# fbd-v1.net
KiCad netlist of a schematic drawn in EAGLE
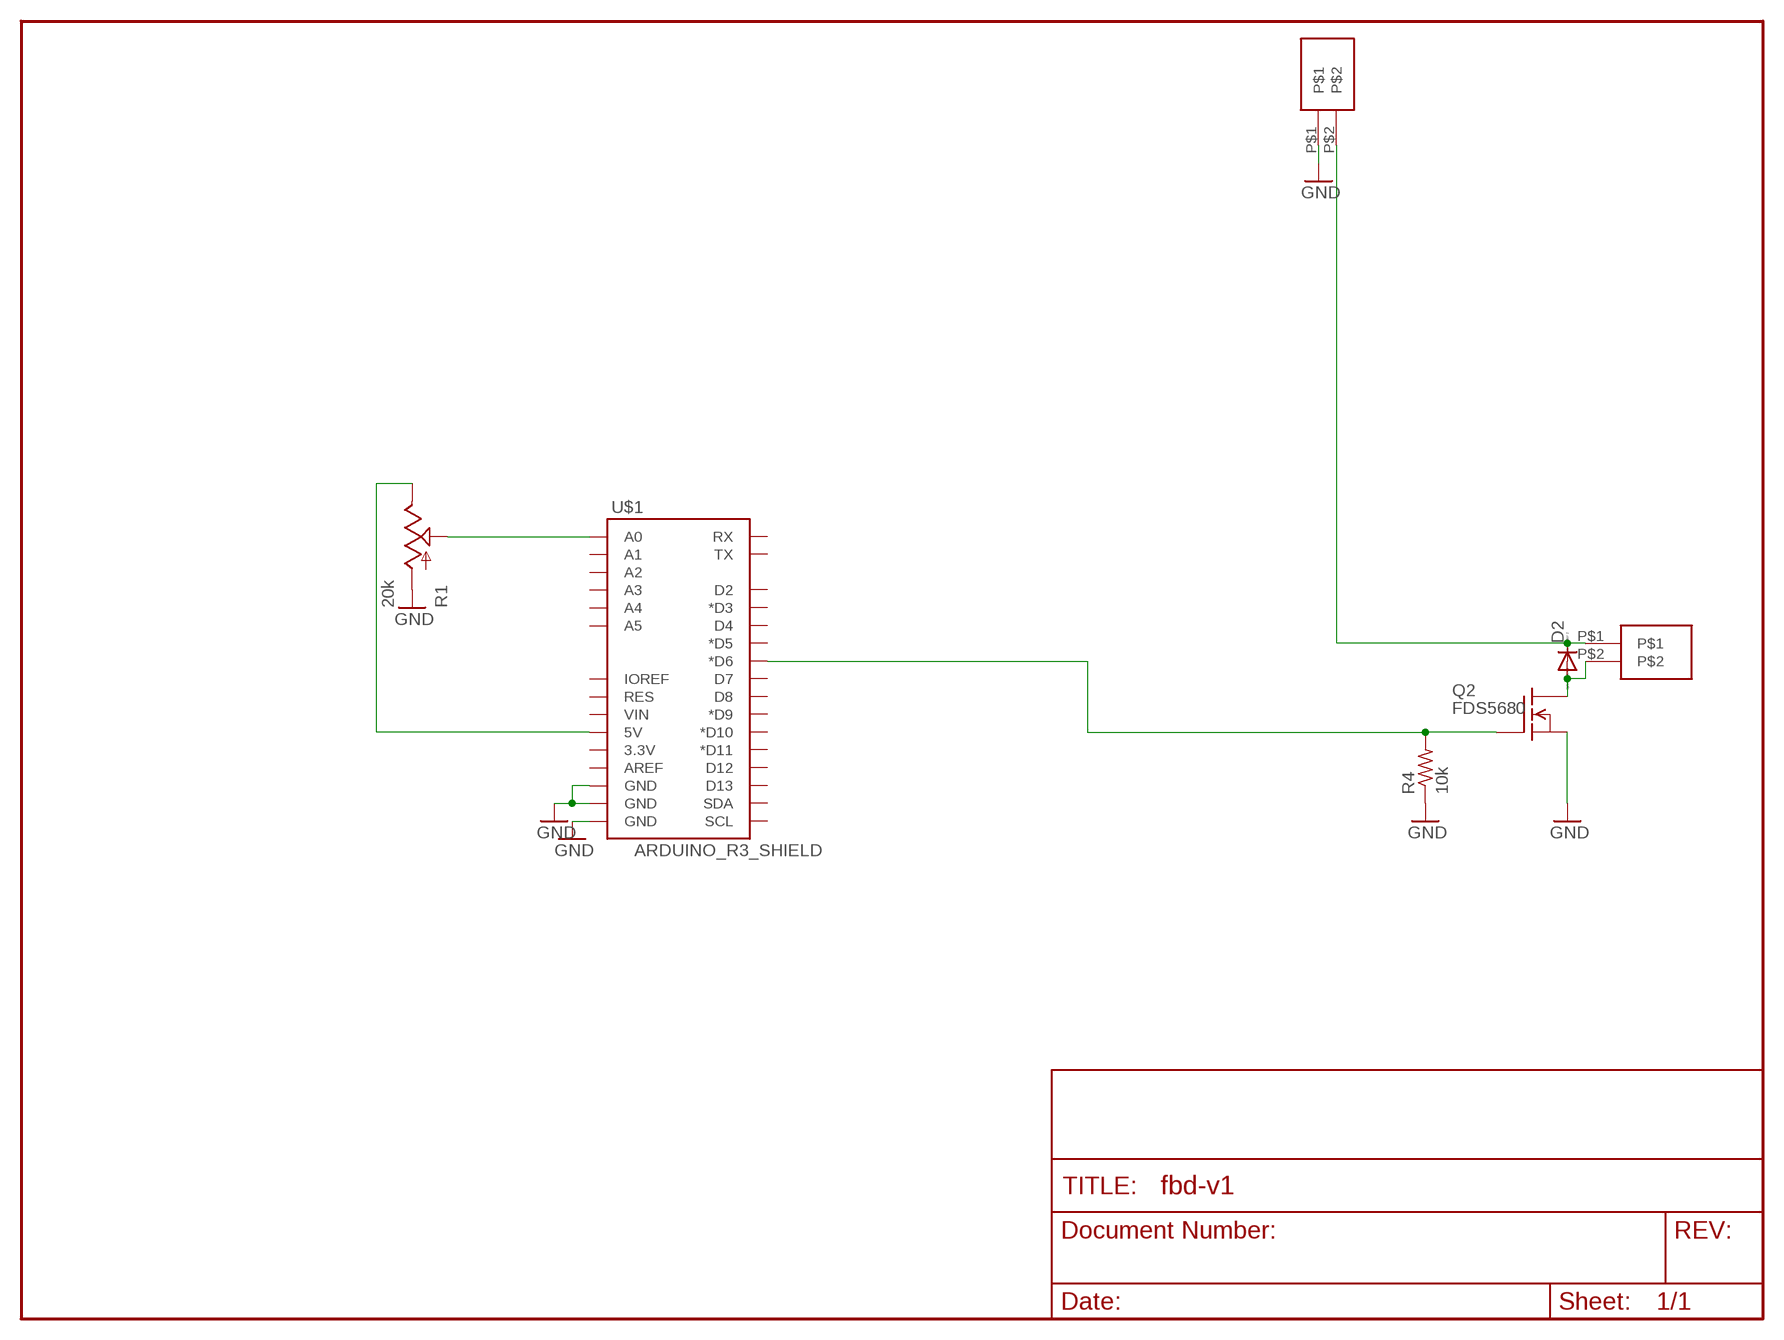
[diagram p0: schematic, sheet 1]

(export (version "E")
  (design (tool "Eeschema 10.0.6"))
  (components
    (comp (ref "D2")
      (value "DIODE-DO-214AC")
      (footprint "eagle-import:DO-214AC")
      (libsource (lib "eagle-import") (part "DIODE-DO-214AC"))
    )
    (comp (ref "Q2")
      (value "FDS5680")
      (footprint "eagle-import:SO-8")
      (libsource (lib "eagle-import") (part "FDS5680"))
    )
    (comp (ref "R1")
      (value "20k")
      (footprint "eagle-import:ALPS_POT_KIT")
      (libsource (lib "eagle-import") (part "POTALPS-KIT"))
    )
    (comp (ref "R4")
      (value "10k")
      (footprint "eagle-import:R0603")
      (libsource (lib "eagle-import") (part "R-US_R0603"))
    )
    (comp (ref "U$1")
      (value "ARDUINO_R3_SHIELD")
      (footprint "eagle-import:UNO_R3_SHIELD")
      (libsource (lib "eagle-import") (part "ARDUINO_R3_SHIELD"))
    )
    (comp (ref "X3")
      (value "SPRING-TERMINAL")
      (footprint "eagle-import:SPRING-TERMINAL")
      (libsource (lib "eagle-import") (part "SPRING-TERMINAL"))
    )
    (comp (ref "X5")
      (value "SPRING-TERMINAL")
      (footprint "eagle-import:SPRING-TERMINAL")
      (libsource (lib "eagle-import") (part "SPRING-TERMINAL"))
    )
  )
  (nets
    (net (code "1") (name "GND") (class "Default")
      (node (ref "Q2") (pin "1") (pinfunction "S_1") (pintype "passive"))
      (node (ref "Q2") (pin "2") (pinfunction "S_2") (pintype "passive"))
      (node (ref "Q2") (pin "3") (pinfunction "S_3") (pintype "passive"))
      (node (ref "R1") (pin "P$3") (pinfunction "A_P$3") (pintype "passive"))
      (node (ref "R4") (pin "1") (pinfunction "1_1") (pintype "passive"))
      (node (ref "U$1") (pin "GND@0") (pinfunction "GND_GND@0") (pintype "bidirectional"))
      (node (ref "U$1") (pin "GND@1") (pinfunction "GND_GND@1") (pintype "bidirectional"))
      (node (ref "U$1") (pin "GND@2") (pinfunction "GND_GND@2") (pintype "bidirectional"))
      (node (ref "X3") (pin "P$1") (pinfunction "P$1_P$1") (pintype "bidirectional"))
    )
    (net (code "2") (name "Net-(D2-PadA)") (class "Default")
      (node (ref "D2") (pin "A") (pinfunction "A_A") (pintype "passive"))
      (node (ref "Q2") (pin "5") (pinfunction "D_5") (pintype "passive"))
      (node (ref "Q2") (pin "6") (pinfunction "D_6") (pintype "passive"))
      (node (ref "Q2") (pin "7") (pinfunction "D_7") (pintype "passive"))
      (node (ref "Q2") (pin "8") (pinfunction "D_8") (pintype "passive"))
      (node (ref "X5") (pin "P$2") (pinfunction "P$2_P$2") (pintype "bidirectional"))
    )
    (net (code "3") (name "Net-(D2-PadC)") (class "Default")
      (node (ref "D2") (pin "C") (pinfunction "C_C") (pintype "passive"))
      (node (ref "X3") (pin "P$2") (pinfunction "P$2_P$2") (pintype "bidirectional"))
      (node (ref "X5") (pin "P$1") (pinfunction "P$1_P$1") (pintype "bidirectional"))
    )
    (net (code "4") (name "Net-(Q2-G)") (class "Default")
      (node (ref "Q2") (pin "4") (pinfunction "G_4") (pintype "passive"))
      (node (ref "R4") (pin "2") (pinfunction "2_2") (pintype "passive"))
      (node (ref "U$1") (pin "D6") (pinfunction "*D6_D6") (pintype "bidirectional"))
    )
    (net (code "5") (name "Net-(R1-E)") (class "Default")
      (node (ref "R1") (pin "P$1") (pinfunction "E_P$1") (pintype "passive"))
      (node (ref "U$1") (pin "5V") (pinfunction "5V_5V") (pintype "bidirectional"))
    )
    (net (code "6") (name "Net-(R1-S)") (class "Default")
      (node (ref "R1") (pin "P$2") (pinfunction "S_P$2") (pintype "passive"))
      (node (ref "U$1") (pin "A0") (pinfunction "A0_A0") (pintype "bidirectional"))
    )
    (net (code "7") (name "unconnected-(U$1-*D3-PadD3)") (class "Default")
      (node (ref "U$1") (pin "D3") (pinfunction "*D3_D3") (pintype "bidirectional"))
    )
    (net (code "8") (name "unconnected-(U$1-*D5-PadD5)") (class "Default")
      (node (ref "U$1") (pin "D5") (pinfunction "*D5_D5") (pintype "bidirectional"))
    )
    (net (code "9") (name "unconnected-(U$1-*D9-PadD9)") (class "Default")
      (node (ref "U$1") (pin "D9") (pinfunction "*D9_D9") (pintype "bidirectional"))
    )
    (net (code "10") (name "unconnected-(U$1-*D10-PadD10)") (class "Default")
      (node (ref "U$1") (pin "D10") (pinfunction "*D10_D10") (pintype "bidirectional"))
    )
    (net (code "11") (name "unconnected-(U$1-*D11-PadD11)") (class "Default")
      (node (ref "U$1") (pin "D11") (pinfunction "*D11_D11") (pintype "bidirectional"))
    )
    (net (code "12") (name "unconnected-(U$1-Pad3.3V)") (class "Default")
      (node (ref "U$1") (pin "3.3V") (pinfunction "3.3V_3.3V") (pintype "bidirectional"))
    )
    (net (code "13") (name "unconnected-(U$1-PadA1)") (class "Default")
      (node (ref "U$1") (pin "A1") (pinfunction "A1_A1") (pintype "bidirectional"))
    )
    (net (code "14") (name "unconnected-(U$1-PadA2)") (class "Default")
      (node (ref "U$1") (pin "A2") (pinfunction "A2_A2") (pintype "bidirectional"))
    )
    (net (code "15") (name "unconnected-(U$1-PadA3)") (class "Default")
      (node (ref "U$1") (pin "A3") (pinfunction "A3_A3") (pintype "bidirectional"))
    )
    (net (code "16") (name "unconnected-(U$1-PadA4)") (class "Default")
      (node (ref "U$1") (pin "A4") (pinfunction "A4_A4") (pintype "bidirectional"))
    )
    (net (code "17") (name "unconnected-(U$1-PadA5)") (class "Default")
      (node (ref "U$1") (pin "A5") (pinfunction "A5_A5") (pintype "bidirectional"))
    )
    (net (code "18") (name "unconnected-(U$1-PadAREF)") (class "Default")
      (node (ref "U$1") (pin "AREF") (pinfunction "AREF_AREF") (pintype "bidirectional"))
    )
    (net (code "19") (name "unconnected-(U$1-PadD2)") (class "Default")
      (node (ref "U$1") (pin "D2") (pinfunction "D2_D2") (pintype "bidirectional"))
    )
    (net (code "20") (name "unconnected-(U$1-PadD4)") (class "Default")
      (node (ref "U$1") (pin "D4") (pinfunction "D4_D4") (pintype "bidirectional"))
    )
    (net (code "21") (name "unconnected-(U$1-PadD7)") (class "Default")
      (node (ref "U$1") (pin "D7") (pinfunction "D7_D7") (pintype "bidirectional"))
    )
    (net (code "22") (name "unconnected-(U$1-PadD8)") (class "Default")
      (node (ref "U$1") (pin "D8") (pinfunction "D8_D8") (pintype "bidirectional"))
    )
    (net (code "23") (name "unconnected-(U$1-PadD12)") (class "Default")
      (node (ref "U$1") (pin "D12") (pinfunction "D12_D12") (pintype "bidirectional"))
    )
    (net (code "24") (name "unconnected-(U$1-PadD13)") (class "Default")
      (node (ref "U$1") (pin "D13") (pinfunction "D13_D13") (pintype "bidirectional"))
    )
    (net (code "25") (name "unconnected-(U$1-PadIOREF)") (class "Default")
      (node (ref "U$1") (pin "IOREF") (pinfunction "IOREF_IOREF") (pintype "bidirectional"))
    )
    (net (code "26") (name "unconnected-(U$1-PadRES)") (class "Default")
      (node (ref "U$1") (pin "RES") (pinfunction "RES_RES") (pintype "bidirectional"))
    )
    (net (code "27") (name "unconnected-(U$1-PadRX)") (class "Default")
      (node (ref "U$1") (pin "RX") (pinfunction "RX_RX") (pintype "bidirectional"))
    )
    (net (code "28") (name "unconnected-(U$1-PadSCL)") (class "Default")
      (node (ref "U$1") (pin "SCL") (pinfunction "SCL_SCL") (pintype "bidirectional"))
    )
    (net (code "29") (name "unconnected-(U$1-PadSDA)") (class "Default")
      (node (ref "U$1") (pin "SDA") (pinfunction "SDA_SDA") (pintype "bidirectional"))
    )
    (net (code "30") (name "unconnected-(U$1-PadTX)") (class "Default")
      (node (ref "U$1") (pin "TX") (pinfunction "TX_TX") (pintype "bidirectional"))
    )
    (net (code "31") (name "unconnected-(U$1-PadVIN)") (class "Default")
      (node (ref "U$1") (pin "VIN") (pinfunction "VIN_VIN") (pintype "bidirectional"))
    )
  )
)
